# CAN_IFC.net
KiCad netlist of a schematic drawn in Altium Designer
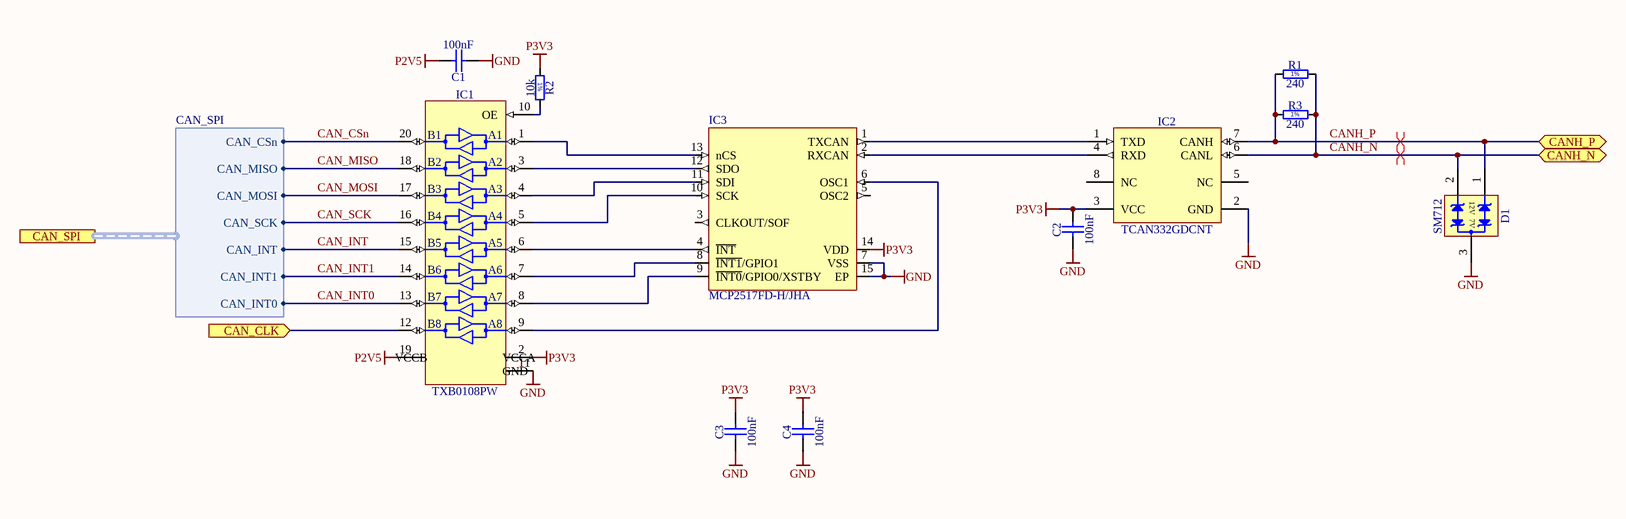
[diagram p0: CAN_IFC.SchDoc]

(export (version "E")
  (design (tool "Eeschema 10.0.6"))
  (components
    (comp (ref "C1")
      (value "100nF")
      (footprint "CAPC1005X55N")
      (description "Non-polarised capacitor")
      (fields
        (field (name "PART NUMBER") "CC0402_100NF_16V_10%_X5R")
        (field (name "VOLTAGE") "16V")
        (field (name "AUTHOR") "CERN DEM JLC")
      )
      (libsource (lib "Capacitors") (part "Capacitor - non polarized"))
    )
    (comp (ref "C2")
      (value "100nF")
      (footprint "CAPC1005X55N")
      (description "Non-polarised capacitor")
      (fields
        (field (name "PART NUMBER") "CC0402_100NF_16V_10%_X5R")
        (field (name "VOLTAGE") "16V")
        (field (name "AUTHOR") "CERN DEM JLC")
      )
      (libsource (lib "Capacitors") (part "Capacitor - non polarized"))
    )
    (comp (ref "C3")
      (value "100nF")
      (footprint "CAPC1005X55N")
      (description "Non-polarised capacitor")
      (fields
        (field (name "PART NUMBER") "CC0402_100NF_16V_10%_X5R")
        (field (name "VOLTAGE") "16V")
        (field (name "AUTHOR") "CERN DEM JLC")
      )
      (libsource (lib "Capacitors") (part "Capacitor - non polarized"))
    )
    (comp (ref "C4")
      (value "100nF")
      (footprint "CAPC1005X55N")
      (description "Non-polarised capacitor")
      (fields
        (field (name "PART NUMBER") "CC0402_100NF_16V_10%_X5R")
        (field (name "VOLTAGE") "16V")
        (field (name "AUTHOR") "CERN DEM JLC")
      )
      (libsource (lib "Capacitors") (part "Capacitor - non polarized"))
    )
    (comp (ref "D1")
      (value "SM712")
      (footprint "SOT95P237X112-3N")
      (description "Asymmetrical TVS Diode for Extended Common-Mode RS-485")
      (fields
        (field (name "VOLTAGE") "12V/-7V")
        (field (name "POWER") "400W")
        (field (name "AUTHOR") "CERN DEM JLC")
      )
      (libsource (lib "ICs And Semiconductors") (part "SM712"))
    )
    (comp (ref "IC1")
      (value "TXB0108PW")
      (footprint "SOP65P640X120-20N")
      (fields (field (name "MANUFACTURER") "TEXAS INSTRUMENTS") (field (name "AUTHOR") "CERN DEM MR"))
      (libsource (lib "ICs And Semiconductors") (part "TXB0108PW"))
    )
    (comp (ref "IC2")
      (value "TCAN332GDCNT")
      (footprint "SOT65P280X145-8N")
      (description "3.3V CAN Transceivers with CAN FD (Flexible Data Rate)")
      (fields (field (name "MANUFACTURER") "TEXAS INSTRUMENTS") (field (name "AUTHOR") "CERN DEM JLC"))
      (libsource (lib "ICs And Semiconductors") (part "TCAN332"))
    )
    (comp (ref "IC3")
      (value "MCP2517FD-H/JHA")
      (footprint "SON65P300X90_HS-15N")
      (description "External CAN FD Controller with SPI Interface")
      (fields (field (name "MANUFACTURER") "Microchip"))
      (libsource (lib "LIBRARY_SCH") (part "IFC_MCP2517"))
    )
    (comp (ref "R1")
      (value "240")
      (footprint "RESC2012X60N")
      (description "Resistor - 1%")
      (fields
        (field (name "PART NUMBER") "R0805_240R_1%_0.125W_100PPM")
        (field (name "POWER") "0.125W")
        (field (name "AUTHOR") "CERN DEM JLC")
      )
      (libsource (lib "Resistors") (part "Resistor - 1%"))
    )
    (comp (ref "R2")
      (value "10k")
      (footprint "RESC1005X40N")
      (description "Resistor - 1%")
      (fields
        (field (name "PART NUMBER") "R0402_10K_1%_0.0625W_100PPM")
        (field (name "POWER") "0.0625W")
        (field (name "AUTHOR") "CERN DEM JLC")
      )
      (libsource (lib "Resistors") (part "Resistor - 1%"))
    )
    (comp (ref "R3")
      (value "240")
      (footprint "RESC2012X60N")
      (description "Resistor - 1%")
      (fields
        (field (name "PART NUMBER") "R0805_240R_1%_0.125W_100PPM")
        (field (name "POWER") "0.125W")
        (field (name "AUTHOR") "CERN DEM JLC")
      )
      (libsource (lib "Resistors") (part "Resistor - 1%"))
    )
  )
  (nets
    (net (code "2") (name "/CANH_N") (class "Default")
      (node (ref "D1") (pin "2") (pinfunction "I/O2_2") (pintype "passive"))
      (node (ref "IC2") (pin "6") (pinfunction "CANL_6") (pintype "bidirectional"))
      (node (ref "R1") (pin "2") (pinfunction "2_2") (pintype "passive"))
      (node (ref "R3") (pin "2") (pinfunction "2_2") (pintype "passive"))
    )
    (net (code "3") (name "/CANH_P") (class "Default")
      (node (ref "D1") (pin "1") (pinfunction "I/O1_1") (pintype "passive"))
      (node (ref "IC2") (pin "7") (pinfunction "CANH_7") (pintype "bidirectional"))
      (node (ref "R1") (pin "1") (pinfunction "1_1") (pintype "passive"))
      (node (ref "R3") (pin "1") (pinfunction "1_1") (pintype "passive"))
    )
    (net (code "4") (name "/CAN_CLK") (class "Default")
      (node (ref "IC1") (pin "12") (pinfunction "B8_12") (pintype "bidirectional"))
    )
    (net (code "5") (name "/CAN_CSn") (class "Default")
      (node (ref "IC1") (pin "20") (pinfunction "B1_20") (pintype "bidirectional"))
    )
    (net (code "6") (name "/CAN_INT") (class "Default")
      (node (ref "IC1") (pin "15") (pinfunction "B5_15") (pintype "bidirectional"))
    )
    (net (code "7") (name "/CAN_INT0") (class "Default")
      (node (ref "IC1") (pin "13") (pinfunction "B7_13") (pintype "bidirectional"))
    )
    (net (code "8") (name "/CAN_INT1") (class "Default")
      (node (ref "IC1") (pin "14") (pinfunction "B6_14") (pintype "bidirectional"))
    )
    (net (code "9") (name "/CAN_MISO") (class "Default")
      (node (ref "IC1") (pin "18") (pinfunction "B2_18") (pintype "bidirectional"))
    )
    (net (code "10") (name "/CAN_MOSI") (class "Default")
      (node (ref "IC1") (pin "17") (pinfunction "B3_17") (pintype "bidirectional"))
    )
    (net (code "11") (name "/CAN_SCK") (class "Default")
      (node (ref "IC1") (pin "16") (pinfunction "B4_16") (pintype "bidirectional"))
    )
    (net (code "13") (name "GND") (class "Default")
      (node (ref "C1") (pin "1") (pinfunction "1_1") (pintype "passive"))
      (node (ref "C2") (pin "1") (pinfunction "1_1") (pintype "passive"))
      (node (ref "C3") (pin "1") (pinfunction "1_1") (pintype "passive"))
      (node (ref "C4") (pin "1") (pinfunction "1_1") (pintype "passive"))
      (node (ref "D1") (pin "3") (pinfunction "GND_3") (pintype "passive"))
      (node (ref "IC1") (pin "11") (pinfunction "GND_11") (pintype "power_in"))
      (node (ref "IC2") (pin "2") (pinfunction "GND_2") (pintype "power_in"))
      (node (ref "IC3") (pin "15") (pinfunction "EP_15") (pintype "power_in"))
      (node (ref "IC3") (pin "7") (pinfunction "VSS_7") (pintype "power_in"))
    )
    (net (code "14") (name "Net-(IC1-A1)") (class "Default")
      (node (ref "IC1") (pin "1") (pinfunction "A1_1") (pintype "bidirectional"))
      (node (ref "IC3") (pin "13") (pinfunction "nCS_13") (pintype "input"))
    )
    (net (code "15") (name "Net-(IC1-A2)") (class "Default")
      (node (ref "IC1") (pin "3") (pinfunction "A2_3") (pintype "bidirectional"))
      (node (ref "IC3") (pin "12") (pinfunction "SDO_12") (pintype "output"))
    )
    (net (code "16") (name "Net-(IC1-A3)") (class "Default")
      (node (ref "IC1") (pin "4") (pinfunction "A3_4") (pintype "bidirectional"))
      (node (ref "IC3") (pin "11") (pinfunction "SDI_11") (pintype "input"))
    )
    (net (code "17") (name "Net-(IC1-A4)") (class "Default")
      (node (ref "IC1") (pin "5") (pinfunction "A4_5") (pintype "bidirectional"))
      (node (ref "IC3") (pin "10") (pinfunction "SCK_10") (pintype "input"))
    )
    (net (code "18") (name "Net-(IC1-A5)") (class "Default")
      (node (ref "IC1") (pin "6") (pinfunction "A5_6") (pintype "bidirectional"))
      (node (ref "IC3") (pin "4") (pinfunction "~{INT}_4") (pintype "output"))
    )
    (net (code "19") (name "Net-(IC1-A6)") (class "Default")
      (node (ref "IC1") (pin "7") (pinfunction "A6_7") (pintype "bidirectional"))
      (node (ref "IC3") (pin "8") (pinfunction "~{INT1}/GPIO1_8") (pintype "bidirectional"))
    )
    (net (code "20") (name "Net-(IC1-A7)") (class "Default")
      (node (ref "IC1") (pin "8") (pinfunction "A7_8") (pintype "bidirectional"))
      (node (ref "IC3") (pin "9") (pinfunction "~{INT0}/GPIO0/XSTBY_9") (pintype "bidirectional"))
    )
    (net (code "21") (name "Net-(IC1-A8)") (class "Default")
      (node (ref "IC1") (pin "9") (pinfunction "A8_9") (pintype "bidirectional"))
      (node (ref "IC3") (pin "6") (pinfunction "OSC1_6") (pintype "input"))
    )
    (net (code "22") (name "Net-(IC1-OE)") (class "Default")
      (node (ref "IC1") (pin "10") (pinfunction "OE_10") (pintype "input"))
      (node (ref "R2") (pin "2") (pinfunction "2_2") (pintype "passive"))
    )
    (net (code "23") (name "Net-(IC2-RXD)") (class "Default")
      (node (ref "IC2") (pin "4") (pinfunction "RXD_4") (pintype "output"))
      (node (ref "IC3") (pin "2") (pinfunction "RXCAN_2") (pintype "input"))
    )
    (net (code "24") (name "Net-(IC2-TXD)") (class "Default")
      (node (ref "IC2") (pin "1") (pinfunction "TXD_1") (pintype "input"))
      (node (ref "IC3") (pin "1") (pinfunction "TXCAN_1") (pintype "output"))
    )
    (net (code "25") (name "P2V5") (class "Default")
      (node (ref "C1") (pin "2") (pinfunction "2_2") (pintype "passive"))
      (node (ref "IC1") (pin "19") (pinfunction "Vccb_19") (pintype "power_in"))
    )
    (net (code "26") (name "P3V3") (class "Default")
      (node (ref "C2") (pin "2") (pinfunction "2_2") (pintype "passive"))
      (node (ref "C3") (pin "2") (pinfunction "2_2") (pintype "passive"))
      (node (ref "C4") (pin "2") (pinfunction "2_2") (pintype "passive"))
      (node (ref "IC1") (pin "2") (pinfunction "Vcca_2") (pintype "power_in"))
      (node (ref "IC2") (pin "3") (pinfunction "VCC_3") (pintype "power_in"))
      (node (ref "IC3") (pin "14") (pinfunction "VDD_14") (pintype "power_in"))
      (node (ref "R2") (pin "1") (pinfunction "1_1") (pintype "passive"))
    )
    (net (code "27") (name "unconnected-(IC2-NC-Pad5)") (class "Default")
      (node (ref "IC2") (pin "5") (pinfunction "NC_5") (pintype "passive"))
    )
    (net (code "28") (name "unconnected-(IC2-NC-Pad8)") (class "Default")
      (node (ref "IC2") (pin "8") (pinfunction "NC_8") (pintype "passive"))
    )
    (net (code "29") (name "unconnected-(IC3-CLKOUT{slash}SOF-Pad3)") (class "Default")
      (node (ref "IC3") (pin "3") (pinfunction "CLKOUT/SOF_3") (pintype "output"))
    )
    (net (code "30") (name "unconnected-(IC3-OSC2-Pad5)") (class "Default")
      (node (ref "IC3") (pin "5") (pinfunction "OSC2_5") (pintype "output"))
    )
  )
)
